# Sh2560.net
KiCad netlist of a schematic drawn in EAGLE
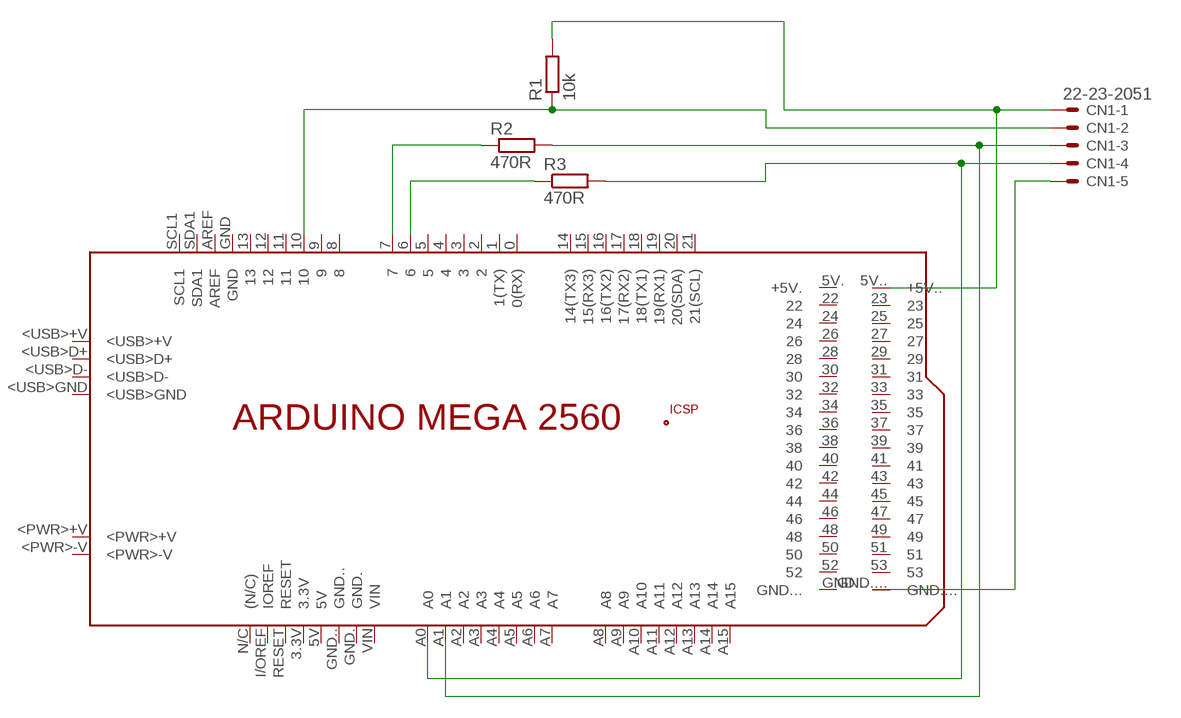
[diagram p0: schematic, sheet 1]

(export (version "E")
  (design (tool "Eeschema 10.0.6"))
  (components
    (comp (ref "CN1")
      (value "22-23-2051")
      (footprint "eagle-import:22-23-2051")
      (fields (field (name "MF") "MOLEX"))
      (libsource (lib "eagle-import") (part "22-23-2051"))
    )
    (comp (ref "PCB1")
      (value "ARDUINO_MEGA2560")
      (footprint "eagle-import:ARDUINO_MEGA2560")
      (libsource (lib "eagle-import") (part "ARDUINO_MEGA2560"))
    )
    (comp (ref "R1")
      (value "10k")
      (footprint "eagle-import:0207_5V")
      (libsource (lib "eagle-import") (part "R-EU_0207/5V"))
    )
    (comp (ref "R2")
      (value "470R")
      (footprint "eagle-import:0207_5V")
      (libsource (lib "eagle-import") (part "R-EU_0207/5V"))
    )
    (comp (ref "R3")
      (value "470R")
      (footprint "eagle-import:0207_5V")
      (libsource (lib "eagle-import") (part "R-EU_0207/5V"))
    )
  )
  (nets
    (net (code "1") (name "Net-(CN1A-S)") (class "Default")
      (node (ref "CN1") (pin "1") (pinfunction "S_1") (pintype "passive"))
      (node (ref "R1") (pin "2") (pinfunction "2_2") (pintype "passive"))
    )
    (net (code "2") (name "Net-(CN1B-S)") (class "Default")
      (node (ref "CN1") (pin "2") (pinfunction "S_2") (pintype "passive"))
      (node (ref "PCB1") (pin "10") (pinfunction "10_10") (pintype "bidirectional"))
      (node (ref "R1") (pin "1") (pinfunction "1_1") (pintype "passive"))
    )
    (net (code "3") (name "Net-(CN1C-S)") (class "Default")
      (node (ref "CN1") (pin "3") (pinfunction "S_3") (pintype "passive"))
      (node (ref "PCB1") (pin "A1") (pinfunction "A1_A1") (pintype "bidirectional"))
      (node (ref "R2") (pin "2") (pinfunction "2_2") (pintype "passive"))
    )
    (net (code "4") (name "Net-(CN1D-S)") (class "Default")
      (node (ref "CN1") (pin "4") (pinfunction "S_4") (pintype "passive"))
      (node (ref "PCB1") (pin "A0") (pinfunction "A0_A0") (pintype "bidirectional"))
      (node (ref "R3") (pin "2") (pinfunction "2_2") (pintype "passive"))
    )
    (net (code "5") (name "Net-(CN1E-S)") (class "Default")
      (node (ref "CN1") (pin "5") (pinfunction "S_5") (pintype "passive"))
      (node (ref "PCB1") (pin "GND....") (pinfunction "GND...._GND....") (pintype "bidirectional"))
    )
    (net (code "6") (name "Net-(PCB1-Pad6)") (class "Default")
      (node (ref "PCB1") (pin "6") (pinfunction "6_6") (pintype "bidirectional"))
      (node (ref "R3") (pin "1") (pinfunction "1_1") (pintype "passive"))
    )
    (net (code "7") (name "Net-(PCB1-Pad7)") (class "Default")
      (node (ref "PCB1") (pin "7") (pinfunction "7_7") (pintype "bidirectional"))
      (node (ref "R2") (pin "1") (pinfunction "1_1") (pintype "passive"))
    )
    (net (code "8") (name "unconnected-(PCB1-(N{slash}C)-PadN{slash}C)") (class "Default")
      (node (ref "PCB1") (pin "N/C") (pinfunction "(N/C)_N/C") (pintype "bidirectional"))
    )
    (net (code "9") (name "unconnected-(PCB1-+5V.-Pad5V.)") (class "Default")
      (node (ref "PCB1") (pin "5V.") (pinfunction "+5V._5V.") (pintype "bidirectional"))
    )
    (net (code "10") (name "unconnected-(PCB1-+5V..-Pad5V..)") (class "Default")
      (node (ref "PCB1") (pin "5V..") (pinfunction "+5V.._5V..") (pintype "bidirectional"))
    )
    (net (code "11") (name "unconnected-(PCB1-0(RX)-Pad0)") (class "Default")
      (node (ref "PCB1") (pin "0") (pinfunction "0(RX)_0") (pintype "bidirectional"))
    )
    (net (code "12") (name "unconnected-(PCB1-1(TX)-Pad1)") (class "Default")
      (node (ref "PCB1") (pin "1") (pinfunction "1(TX)_1") (pintype "bidirectional"))
    )
    (net (code "13") (name "unconnected-(PCB1-14(TX3)-Pad14)") (class "Default")
      (node (ref "PCB1") (pin "14") (pinfunction "14(TX3)_14") (pintype "bidirectional"))
    )
    (net (code "14") (name "unconnected-(PCB1-15(RX3)-Pad15)") (class "Default")
      (node (ref "PCB1") (pin "15") (pinfunction "15(RX3)_15") (pintype "bidirectional"))
    )
    (net (code "15") (name "unconnected-(PCB1-16(TX2)-Pad16)") (class "Default")
      (node (ref "PCB1") (pin "16") (pinfunction "16(TX2)_16") (pintype "bidirectional"))
    )
    (net (code "16") (name "unconnected-(PCB1-17(RX2)-Pad17)") (class "Default")
      (node (ref "PCB1") (pin "17") (pinfunction "17(RX2)_17") (pintype "bidirectional"))
    )
    (net (code "17") (name "unconnected-(PCB1-18(TX1)-Pad18)") (class "Default")
      (node (ref "PCB1") (pin "18") (pinfunction "18(TX1)_18") (pintype "bidirectional"))
    )
    (net (code "18") (name "unconnected-(PCB1-19(RX1)-Pad19)") (class "Default")
      (node (ref "PCB1") (pin "19") (pinfunction "19(RX1)_19") (pintype "bidirectional"))
    )
    (net (code "19") (name "unconnected-(PCB1-20(SDA)-Pad20)") (class "Default")
      (node (ref "PCB1") (pin "20") (pinfunction "20(SDA)_20") (pintype "bidirectional"))
    )
    (net (code "20") (name "unconnected-(PCB1-21(SCL)-Pad21)") (class "Default")
      (node (ref "PCB1") (pin "21") (pinfunction "21(SCL)_21") (pintype "bidirectional"))
    )
    (net (code "21") (name "unconnected-(PCB1-IOREF-PadI{slash}OREF)") (class "Default")
      (node (ref "PCB1") (pin "I/OREF") (pinfunction "IOREF_I/OREF") (pintype "bidirectional"))
    )
    (net (code "22") (name "unconnected-(PCB1-Pad+5V_)") (class "Default")
      (node (ref "PCB1") (pin "+5V_") (pinfunction "+5V__+5V_") (pintype "bidirectional"))
    )
    (net (code "23") (name "unconnected-(PCB1-Pad2)") (class "Default")
      (node (ref "PCB1") (pin "2") (pinfunction "2_2") (pintype "bidirectional"))
    )
    (net (code "24") (name "unconnected-(PCB1-Pad3)") (class "Default")
      (node (ref "PCB1") (pin "3") (pinfunction "3_3") (pintype "bidirectional"))
    )
    (net (code "25") (name "unconnected-(PCB1-Pad3.3V)") (class "Default")
      (node (ref "PCB1") (pin "3.3V") (pinfunction "3.3V_3.3V") (pintype "bidirectional"))
    )
    (net (code "26") (name "unconnected-(PCB1-Pad4)") (class "Default")
      (node (ref "PCB1") (pin "4") (pinfunction "4_4") (pintype "bidirectional"))
    )
    (net (code "27") (name "unconnected-(PCB1-Pad5)") (class "Default")
      (node (ref "PCB1") (pin "5") (pinfunction "5_5") (pintype "bidirectional"))
    )
    (net (code "28") (name "unconnected-(PCB1-Pad5V)") (class "Default")
      (node (ref "PCB1") (pin "5V") (pinfunction "5V_5V") (pintype "bidirectional"))
    )
    (net (code "29") (name "unconnected-(PCB1-Pad8)") (class "Default")
      (node (ref "PCB1") (pin "8") (pinfunction "8_8") (pintype "bidirectional"))
    )
    (net (code "30") (name "unconnected-(PCB1-Pad9)") (class "Default")
      (node (ref "PCB1") (pin "9") (pinfunction "9_9") (pintype "bidirectional"))
    )
    (net (code "31") (name "unconnected-(PCB1-Pad11)") (class "Default")
      (node (ref "PCB1") (pin "11") (pinfunction "11_11") (pintype "bidirectional"))
    )
    (net (code "32") (name "unconnected-(PCB1-Pad12)") (class "Default")
      (node (ref "PCB1") (pin "12") (pinfunction "12_12") (pintype "bidirectional"))
    )
    (net (code "33") (name "unconnected-(PCB1-Pad13)") (class "Default")
      (node (ref "PCB1") (pin "13") (pinfunction "13_13") (pintype "bidirectional"))
    )
    (net (code "34") (name "unconnected-(PCB1-Pad22)") (class "Default")
      (node (ref "PCB1") (pin "22") (pinfunction "22_22") (pintype "bidirectional"))
    )
    (net (code "35") (name "unconnected-(PCB1-Pad23)") (class "Default")
      (node (ref "PCB1") (pin "23") (pinfunction "23_23") (pintype "bidirectional"))
    )
    (net (code "36") (name "unconnected-(PCB1-Pad24)") (class "Default")
      (node (ref "PCB1") (pin "24") (pinfunction "24_24") (pintype "bidirectional"))
    )
    (net (code "37") (name "unconnected-(PCB1-Pad25)") (class "Default")
      (node (ref "PCB1") (pin "25") (pinfunction "25_25") (pintype "bidirectional"))
    )
    (net (code "38") (name "unconnected-(PCB1-Pad26)") (class "Default")
      (node (ref "PCB1") (pin "26") (pinfunction "26_26") (pintype "bidirectional"))
    )
    (net (code "39") (name "unconnected-(PCB1-Pad27)") (class "Default")
      (node (ref "PCB1") (pin "27") (pinfunction "27_27") (pintype "bidirectional"))
    )
    (net (code "40") (name "unconnected-(PCB1-Pad28)") (class "Default")
      (node (ref "PCB1") (pin "28") (pinfunction "28_28") (pintype "bidirectional"))
    )
    (net (code "41") (name "unconnected-(PCB1-Pad29)") (class "Default")
      (node (ref "PCB1") (pin "29") (pinfunction "29_29") (pintype "bidirectional"))
    )
    (net (code "42") (name "unconnected-(PCB1-Pad30)") (class "Default")
      (node (ref "PCB1") (pin "30") (pinfunction "30_30") (pintype "bidirectional"))
    )
    (net (code "43") (name "unconnected-(PCB1-Pad31)") (class "Default")
      (node (ref "PCB1") (pin "31") (pinfunction "31_31") (pintype "bidirectional"))
    )
    (net (code "44") (name "unconnected-(PCB1-Pad32)") (class "Default")
      (node (ref "PCB1") (pin "32") (pinfunction "32_32") (pintype "bidirectional"))
    )
    (net (code "45") (name "unconnected-(PCB1-Pad33)") (class "Default")
      (node (ref "PCB1") (pin "33") (pinfunction "33_33") (pintype "bidirectional"))
    )
    (net (code "46") (name "unconnected-(PCB1-Pad34)") (class "Default")
      (node (ref "PCB1") (pin "34") (pinfunction "34_34") (pintype "bidirectional"))
    )
    (net (code "47") (name "unconnected-(PCB1-Pad35)") (class "Default")
      (node (ref "PCB1") (pin "35") (pinfunction "35_35") (pintype "bidirectional"))
    )
    (net (code "48") (name "unconnected-(PCB1-Pad36)") (class "Default")
      (node (ref "PCB1") (pin "36") (pinfunction "36_36") (pintype "bidirectional"))
    )
    (net (code "49") (name "unconnected-(PCB1-Pad37)") (class "Default")
      (node (ref "PCB1") (pin "37") (pinfunction "37_37") (pintype "bidirectional"))
    )
    (net (code "50") (name "unconnected-(PCB1-Pad38)") (class "Default")
      (node (ref "PCB1") (pin "38") (pinfunction "38_38") (pintype "bidirectional"))
    )
    (net (code "51") (name "unconnected-(PCB1-Pad39)") (class "Default")
      (node (ref "PCB1") (pin "39") (pinfunction "39_39") (pintype "bidirectional"))
    )
    (net (code "52") (name "unconnected-(PCB1-Pad40)") (class "Default")
      (node (ref "PCB1") (pin "40") (pinfunction "40_40") (pintype "bidirectional"))
    )
    (net (code "53") (name "unconnected-(PCB1-Pad41)") (class "Default")
      (node (ref "PCB1") (pin "41") (pinfunction "41_41") (pintype "bidirectional"))
    )
    (net (code "54") (name "unconnected-(PCB1-Pad42)") (class "Default")
      (node (ref "PCB1") (pin "42") (pinfunction "42_42") (pintype "bidirectional"))
    )
    (net (code "55") (name "unconnected-(PCB1-Pad43)") (class "Default")
      (node (ref "PCB1") (pin "43") (pinfunction "43_43") (pintype "bidirectional"))
    )
    (net (code "56") (name "unconnected-(PCB1-Pad44)") (class "Default")
      (node (ref "PCB1") (pin "44") (pinfunction "44_44") (pintype "bidirectional"))
    )
    (net (code "57") (name "unconnected-(PCB1-Pad45)") (class "Default")
      (node (ref "PCB1") (pin "45") (pinfunction "45_45") (pintype "bidirectional"))
    )
    (net (code "58") (name "unconnected-(PCB1-Pad46)") (class "Default")
      (node (ref "PCB1") (pin "46") (pinfunction "46_46") (pintype "bidirectional"))
    )
    (net (code "59") (name "unconnected-(PCB1-Pad47)") (class "Default")
      (node (ref "PCB1") (pin "47") (pinfunction "47_47") (pintype "bidirectional"))
    )
    (net (code "60") (name "unconnected-(PCB1-Pad48)") (class "Default")
      (node (ref "PCB1") (pin "48") (pinfunction "48_48") (pintype "bidirectional"))
    )
    (net (code "61") (name "unconnected-(PCB1-Pad49)") (class "Default")
      (node (ref "PCB1") (pin "49") (pinfunction "49_49") (pintype "bidirectional"))
    )
    (net (code "62") (name "unconnected-(PCB1-Pad50)") (class "Default")
      (node (ref "PCB1") (pin "50") (pinfunction "50_50") (pintype "bidirectional"))
    )
    (net (code "63") (name "unconnected-(PCB1-Pad51)") (class "Default")
      (node (ref "PCB1") (pin "51") (pinfunction "51_51") (pintype "bidirectional"))
    )
    (net (code "64") (name "unconnected-(PCB1-Pad52)") (class "Default")
      (node (ref "PCB1") (pin "52") (pinfunction "52_52") (pintype "bidirectional"))
    )
    (net (code "65") (name "unconnected-(PCB1-Pad53)") (class "Default")
      (node (ref "PCB1") (pin "53") (pinfunction "53_53") (pintype "bidirectional"))
    )
    (net (code "66") (name "unconnected-(PCB1-Pad<PWR>+V)") (class "Default")
      (node (ref "PCB1") (pin "<PWR>+V") (pinfunction "<PWR>+V_<PWR>+V") (pintype "no_connect"))
    )
    (net (code "67") (name "unconnected-(PCB1-Pad<PWR>-V)") (class "Default")
      (node (ref "PCB1") (pin "<PWR>-V") (pinfunction "<PWR>-V_<PWR>-V") (pintype "no_connect"))
    )
    (net (code "68") (name "unconnected-(PCB1-Pad<USB>+V)") (class "Default")
      (node (ref "PCB1") (pin "<USB>+V") (pinfunction "<USB>+V_<USB>+V") (pintype "no_connect"))
    )
    (net (code "69") (name "unconnected-(PCB1-Pad<USB>D+)") (class "Default")
      (node (ref "PCB1") (pin "<USB>D+") (pinfunction "<USB>D+_<USB>D+") (pintype "no_connect"))
    )
    (net (code "70") (name "unconnected-(PCB1-Pad<USB>D-)") (class "Default")
      (node (ref "PCB1") (pin "<USB>D-") (pinfunction "<USB>D-_<USB>D-") (pintype "no_connect"))
    )
    (net (code "71") (name "unconnected-(PCB1-Pad<USB>GND)") (class "Default")
      (node (ref "PCB1") (pin "<USB>GND") (pinfunction "<USB>GND_<USB>GND") (pintype "no_connect"))
    )
    (net (code "72") (name "unconnected-(PCB1-PadA2)") (class "Default")
      (node (ref "PCB1") (pin "A2") (pinfunction "A2_A2") (pintype "bidirectional"))
    )
    (net (code "73") (name "unconnected-(PCB1-PadA3)") (class "Default")
      (node (ref "PCB1") (pin "A3") (pinfunction "A3_A3") (pintype "bidirectional"))
    )
    (net (code "74") (name "unconnected-(PCB1-PadA4)") (class "Default")
      (node (ref "PCB1") (pin "A4") (pinfunction "A4_A4") (pintype "bidirectional"))
    )
    (net (code "75") (name "unconnected-(PCB1-PadA5)") (class "Default")
      (node (ref "PCB1") (pin "A5") (pinfunction "A5_A5") (pintype "bidirectional"))
    )
    (net (code "76") (name "unconnected-(PCB1-PadA6)") (class "Default")
      (node (ref "PCB1") (pin "A6") (pinfunction "A6_A6") (pintype "bidirectional"))
    )
    (net (code "77") (name "unconnected-(PCB1-PadA7)") (class "Default")
      (node (ref "PCB1") (pin "A7") (pinfunction "A7_A7") (pintype "bidirectional"))
    )
    (net (code "78") (name "unconnected-(PCB1-PadA8)") (class "Default")
      (node (ref "PCB1") (pin "A8") (pinfunction "A8_A8") (pintype "bidirectional"))
    )
    (net (code "79") (name "unconnected-(PCB1-PadA9)") (class "Default")
      (node (ref "PCB1") (pin "A9") (pinfunction "A9_A9") (pintype "bidirectional"))
    )
    (net (code "80") (name "unconnected-(PCB1-PadA10)") (class "Default")
      (node (ref "PCB1") (pin "A10") (pinfunction "A10_A10") (pintype "bidirectional"))
    )
    (net (code "81") (name "unconnected-(PCB1-PadA11)") (class "Default")
      (node (ref "PCB1") (pin "A11") (pinfunction "A11_A11") (pintype "bidirectional"))
    )
    (net (code "82") (name "unconnected-(PCB1-PadA12)") (class "Default")
      (node (ref "PCB1") (pin "A12") (pinfunction "A12_A12") (pintype "bidirectional"))
    )
    (net (code "83") (name "unconnected-(PCB1-PadA13)") (class "Default")
      (node (ref "PCB1") (pin "A13") (pinfunction "A13_A13") (pintype "bidirectional"))
    )
    (net (code "84") (name "unconnected-(PCB1-PadA14)") (class "Default")
      (node (ref "PCB1") (pin "A14") (pinfunction "A14_A14") (pintype "bidirectional"))
    )
    (net (code "85") (name "unconnected-(PCB1-PadA15)") (class "Default")
      (node (ref "PCB1") (pin "A15") (pinfunction "A15_A15") (pintype "bidirectional"))
    )
    (net (code "86") (name "unconnected-(PCB1-PadAREF)") (class "Default")
      (node (ref "PCB1") (pin "AREF") (pinfunction "AREF_AREF") (pintype "bidirectional"))
    )
    (net (code "87") (name "unconnected-(PCB1-PadGND)") (class "Default")
      (node (ref "PCB1") (pin "GND") (pinfunction "GND_GND") (pintype "bidirectional"))
    )
    (net (code "88") (name "unconnected-(PCB1-PadGND.)") (class "Default")
      (node (ref "PCB1") (pin "GND.") (pinfunction "GND._GND.") (pintype "bidirectional"))
    )
    (net (code "89") (name "unconnected-(PCB1-PadGND..)") (class "Default")
      (node (ref "PCB1") (pin "GND..") (pinfunction "GND.._GND..") (pintype "bidirectional"))
    )
    (net (code "90") (name "unconnected-(PCB1-PadGND...)") (class "Default")
      (node (ref "PCB1") (pin "GND...") (pinfunction "GND..._GND...") (pintype "bidirectional"))
    )
    (net (code "91") (name "unconnected-(PCB1-PadGND__)") (class "Default")
      (node (ref "PCB1") (pin "GND__") (pinfunction "GND___GND__") (pintype "bidirectional"))
    )
    (net (code "92") (name "unconnected-(PCB1-PadMISO)") (class "Default")
      (node (ref "PCB1") (pin "MISO") (pinfunction "MISO_MISO") (pintype "bidirectional"))
    )
    (net (code "93") (name "unconnected-(PCB1-PadMOSI)") (class "Default")
      (node (ref "PCB1") (pin "MOSI") (pinfunction "MOSI_MOSI") (pintype "bidirectional"))
    )
    (net (code "94") (name "unconnected-(PCB1-PadRESET)") (class "Default")
      (node (ref "PCB1") (pin "RESET") (pinfunction "RESET_RESET") (pintype "bidirectional"))
    )
    (net (code "95") (name "unconnected-(PCB1-PadRESET.)") (class "Default")
      (node (ref "PCB1") (pin "RESET.") (pinfunction "RESET._RESET.") (pintype "bidirectional"))
    )
    (net (code "96") (name "unconnected-(PCB1-PadSCK)") (class "Default")
      (node (ref "PCB1") (pin "SCK") (pinfunction "SCK_SCK") (pintype "bidirectional"))
    )
    (net (code "97") (name "unconnected-(PCB1-PadSCL1)") (class "Default")
      (node (ref "PCB1") (pin "SCL1") (pinfunction "SCL1_SCL1") (pintype "bidirectional"))
    )
    (net (code "98") (name "unconnected-(PCB1-PadSDA1)") (class "Default")
      (node (ref "PCB1") (pin "SDA1") (pinfunction "SDA1_SDA1") (pintype "bidirectional"))
    )
    (net (code "99") (name "unconnected-(PCB1-PadVIN)") (class "Default")
      (node (ref "PCB1") (pin "VIN") (pinfunction "VIN_VIN") (pintype "bidirectional"))
    )
  )
)
